# main.net
KiCad netlist of a schematic drawn in EAGLE
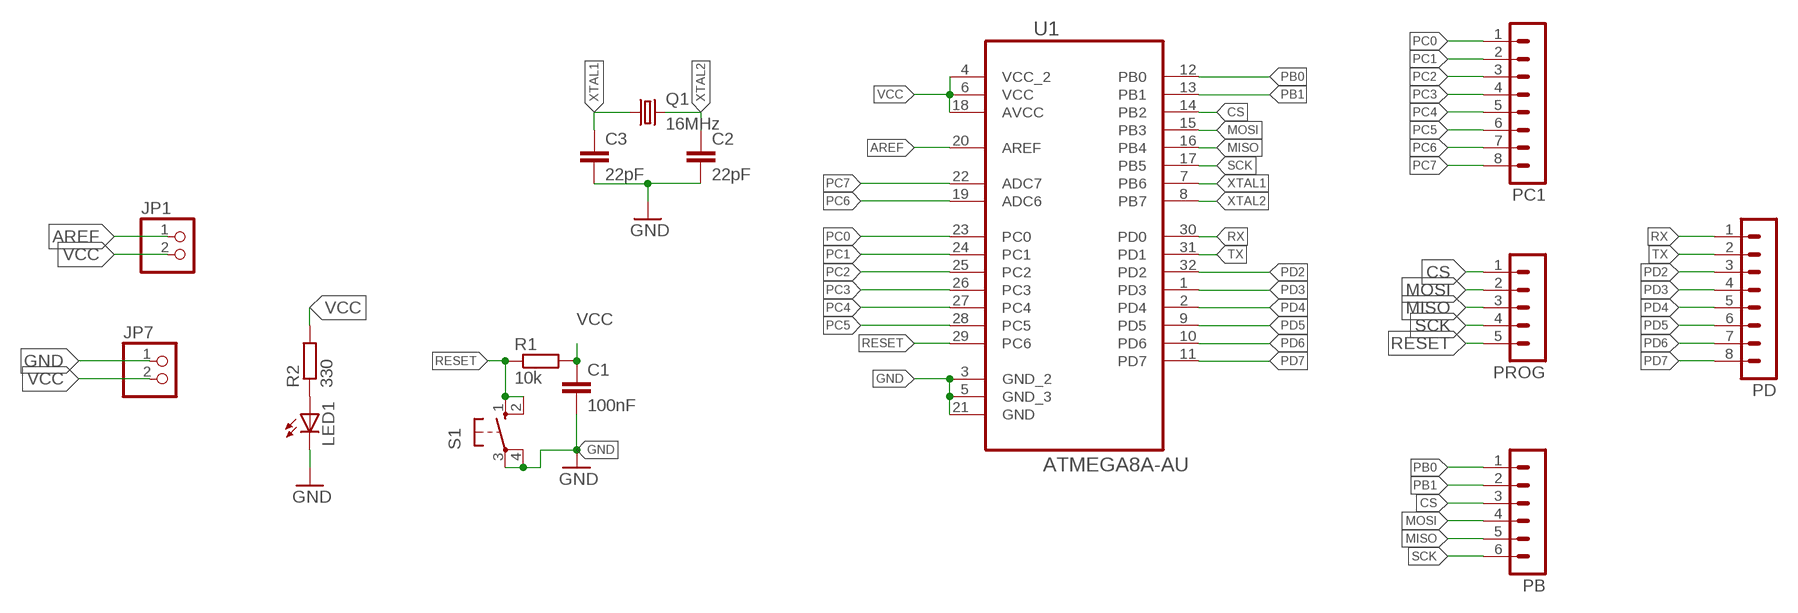
[diagram p0: schematic, sheet 1]

(export (version "E")
  (design (tool "Eeschema 10.0.6"))
  (components
    (comp (ref "C1")
      (value "100nF")
      (footprint "eagle-import:C025-025X050")
      (libsource (lib "eagle-import") (part "C-EU025-025X050"))
    )
    (comp (ref "C2")
      (value "22pF")
      (footprint "eagle-import:C025-025X050")
      (libsource (lib "eagle-import") (part "C-EU025-025X050"))
    )
    (comp (ref "C3")
      (value "22pF")
      (footprint "eagle-import:C025-025X050")
      (libsource (lib "eagle-import") (part "C-EU025-025X050"))
    )
    (comp (ref "JP1")
      (value "PINHD-1X2")
      (footprint "eagle-import:1X02")
      (libsource (lib "eagle-import") (part "PINHD-1X2"))
    )
    (comp (ref "JP7")
      (value "PINHD-1X2")
      (footprint "eagle-import:1X02")
      (libsource (lib "eagle-import") (part "PINHD-1X2"))
    )
    (comp (ref "LED1")
      (value "LED3MM")
      (footprint "eagle-import:LED3MM")
      (libsource (lib "eagle-import") (part "LED3MM"))
    )
    (comp (ref "PB")
      (value "MA06-1")
      (footprint "eagle-import:MA06-1")
      (libsource (lib "eagle-import") (part "MA06-1"))
    )
    (comp (ref "PC1")
      (value "MA08-1")
      (footprint "eagle-import:MA08-1")
      (libsource (lib "eagle-import") (part "MA08-1"))
    )
    (comp (ref "PD")
      (value "MA08-1")
      (footprint "eagle-import:MA08-1")
      (libsource (lib "eagle-import") (part "MA08-1"))
    )
    (comp (ref "PROG")
      (value "MA05-1")
      (footprint "eagle-import:MA05-1")
      (libsource (lib "eagle-import") (part "MA05-1"))
    )
    (comp (ref "Q1")
      (value "16MHz")
      (footprint "eagle-import:HC49_S")
      (libsource (lib "eagle-import") (part "CRYSTALHC49S"))
    )
    (comp (ref "R1")
      (value "10k")
      (footprint "eagle-import:M0805")
      (libsource (lib "eagle-import") (part "resistor_R-EU_M0805"))
    )
    (comp (ref "R2")
      (value "330")
      (footprint "eagle-import:M0805")
      (libsource (lib "eagle-import") (part "R-EU_M0805"))
    )
    (comp (ref "S1")
      (value "10-XX")
      (footprint "eagle-import:B3F-10XX")
      (fields (field (name "MPN") "B3F-1000"))
      (libsource (lib "eagle-import") (part "10-XX"))
    )
    (comp (ref "U1")
      (value "ATMEGA8A-AU")
      (footprint "eagle-import:QFP80P900X900X120-32N")
      (libsource (lib "eagle-import") (part "ATMEGA8A-AU"))
    )
  )
  (nets
    (net (code "1") (name "AREF") (class "Default")
      (node (ref "JP1") (pin "1") (pinfunction "1_1") (pintype "passive"))
      (node (ref "U1") (pin "20") (pinfunction "AREF_20") (pintype "input"))
    )
    (net (code "2") (name "CS") (class "Default")
      (node (ref "PB") (pin "3") (pinfunction "3_3") (pintype "passive"))
      (node (ref "PROG") (pin "1") (pinfunction "1_1") (pintype "passive"))
      (node (ref "U1") (pin "14") (pinfunction "PB2_14") (pintype "passive"))
    )
    (net (code "3") (name "GND") (class "Default")
      (node (ref "C1") (pin "2") (pinfunction "2_2") (pintype "passive"))
      (node (ref "C2") (pin "2") (pinfunction "2_2") (pintype "passive"))
      (node (ref "C3") (pin "2") (pinfunction "2_2") (pintype "passive"))
      (node (ref "JP7") (pin "1") (pinfunction "1_1") (pintype "passive"))
      (node (ref "LED1") (pin "K") (pinfunction "C_K") (pintype "passive"))
      (node (ref "S1") (pin "3") (pinfunction "P_3") (pintype "passive"))
      (node (ref "S1") (pin "4") (pinfunction "P1_4") (pintype "passive"))
      (node (ref "U1") (pin "21") (pinfunction "GND_21") (pintype "passive"))
      (node (ref "U1") (pin "3") (pinfunction "GND_2_3") (pintype "passive"))
      (node (ref "U1") (pin "5") (pinfunction "GND_3_5") (pintype "passive"))
    )
    (net (code "4") (name "MISO") (class "Default")
      (node (ref "PB") (pin "5") (pinfunction "5_5") (pintype "passive"))
      (node (ref "PROG") (pin "3") (pinfunction "3_3") (pintype "passive"))
      (node (ref "U1") (pin "16") (pinfunction "PB4_16") (pintype "passive"))
    )
    (net (code "5") (name "MOSI") (class "Default")
      (node (ref "PB") (pin "4") (pinfunction "4_4") (pintype "passive"))
      (node (ref "PROG") (pin "2") (pinfunction "2_2") (pintype "passive"))
      (node (ref "U1") (pin "15") (pinfunction "PB3_15") (pintype "passive"))
    )
    (net (code "6") (name "Net-(LED1-PadA)") (class "Default")
      (node (ref "LED1") (pin "A") (pinfunction "A_A") (pintype "passive"))
      (node (ref "R2") (pin "1") (pinfunction "1_1") (pintype "passive"))
    )
    (net (code "7") (name "PB0") (class "Default")
      (node (ref "PB") (pin "1") (pinfunction "1_1") (pintype "passive"))
      (node (ref "U1") (pin "12") (pinfunction "PB0_12") (pintype "passive"))
    )
    (net (code "8") (name "PB1") (class "Default")
      (node (ref "PB") (pin "2") (pinfunction "2_2") (pintype "passive"))
      (node (ref "U1") (pin "13") (pinfunction "PB1_13") (pintype "passive"))
    )
    (net (code "9") (name "PC0") (class "Default")
      (node (ref "PC1") (pin "1") (pinfunction "1_1") (pintype "passive"))
      (node (ref "U1") (pin "23") (pinfunction "PC0_23") (pintype "bidirectional"))
    )
    (net (code "10") (name "PC1") (class "Default")
      (node (ref "PC1") (pin "2") (pinfunction "2_2") (pintype "passive"))
      (node (ref "U1") (pin "24") (pinfunction "PC1_24") (pintype "bidirectional"))
    )
    (net (code "11") (name "PC2") (class "Default")
      (node (ref "PC1") (pin "3") (pinfunction "3_3") (pintype "passive"))
      (node (ref "U1") (pin "25") (pinfunction "PC2_25") (pintype "bidirectional"))
    )
    (net (code "12") (name "PC3") (class "Default")
      (node (ref "PC1") (pin "4") (pinfunction "4_4") (pintype "passive"))
      (node (ref "U1") (pin "26") (pinfunction "PC3_26") (pintype "bidirectional"))
    )
    (net (code "13") (name "PC4") (class "Default")
      (node (ref "PC1") (pin "5") (pinfunction "5_5") (pintype "passive"))
      (node (ref "U1") (pin "27") (pinfunction "PC4_27") (pintype "bidirectional"))
    )
    (net (code "14") (name "PC5") (class "Default")
      (node (ref "PC1") (pin "6") (pinfunction "6_6") (pintype "passive"))
      (node (ref "U1") (pin "28") (pinfunction "PC5_28") (pintype "bidirectional"))
    )
    (net (code "15") (name "PC6") (class "Default")
      (node (ref "PC1") (pin "7") (pinfunction "7_7") (pintype "passive"))
      (node (ref "U1") (pin "19") (pinfunction "ADC6_19") (pintype "input"))
    )
    (net (code "16") (name "PC7") (class "Default")
      (node (ref "PC1") (pin "8") (pinfunction "8_8") (pintype "passive"))
      (node (ref "U1") (pin "22") (pinfunction "ADC7_22") (pintype "input"))
    )
    (net (code "17") (name "PD2") (class "Default")
      (node (ref "PD") (pin "3") (pinfunction "3_3") (pintype "passive"))
      (node (ref "U1") (pin "32") (pinfunction "PD2_32") (pintype "bidirectional"))
    )
    (net (code "18") (name "PD3") (class "Default")
      (node (ref "PD") (pin "4") (pinfunction "4_4") (pintype "passive"))
      (node (ref "U1") (pin "1") (pinfunction "PD3_1") (pintype "bidirectional"))
    )
    (net (code "19") (name "PD4") (class "Default")
      (node (ref "PD") (pin "5") (pinfunction "5_5") (pintype "passive"))
      (node (ref "U1") (pin "2") (pinfunction "PD4_2") (pintype "bidirectional"))
    )
    (net (code "20") (name "PD5") (class "Default")
      (node (ref "PD") (pin "6") (pinfunction "6_6") (pintype "passive"))
      (node (ref "U1") (pin "9") (pinfunction "PD5_9") (pintype "passive"))
    )
    (net (code "21") (name "PD6") (class "Default")
      (node (ref "PD") (pin "7") (pinfunction "7_7") (pintype "passive"))
      (node (ref "U1") (pin "10") (pinfunction "PD6_10") (pintype "passive"))
    )
    (net (code "22") (name "PD7") (class "Default")
      (node (ref "PD") (pin "8") (pinfunction "8_8") (pintype "passive"))
      (node (ref "U1") (pin "11") (pinfunction "PD7_11") (pintype "passive"))
    )
    (net (code "23") (name "RESET") (class "Default")
      (node (ref "PROG") (pin "5") (pinfunction "5_5") (pintype "passive"))
      (node (ref "R1") (pin "1") (pinfunction "1_1") (pintype "passive"))
      (node (ref "S1") (pin "1") (pinfunction "S_1") (pintype "passive"))
      (node (ref "S1") (pin "2") (pinfunction "S1_2") (pintype "passive"))
      (node (ref "U1") (pin "29") (pinfunction "PC6_29") (pintype "bidirectional"))
    )
    (net (code "24") (name "RX") (class "Default")
      (node (ref "PD") (pin "1") (pinfunction "1_1") (pintype "passive"))
      (node (ref "U1") (pin "30") (pinfunction "PD0_30") (pintype "bidirectional"))
    )
    (net (code "25") (name "SCK") (class "Default")
      (node (ref "PB") (pin "6") (pinfunction "6_6") (pintype "passive"))
      (node (ref "PROG") (pin "4") (pinfunction "4_4") (pintype "passive"))
      (node (ref "U1") (pin "17") (pinfunction "PB5_17") (pintype "passive"))
    )
    (net (code "26") (name "TX") (class "Default")
      (node (ref "PD") (pin "2") (pinfunction "2_2") (pintype "passive"))
      (node (ref "U1") (pin "31") (pinfunction "PD1_31") (pintype "bidirectional"))
    )
    (net (code "27") (name "VCC") (class "Default")
      (node (ref "C1") (pin "1") (pinfunction "1_1") (pintype "passive"))
      (node (ref "JP1") (pin "2") (pinfunction "2_2") (pintype "passive"))
      (node (ref "JP7") (pin "2") (pinfunction "2_2") (pintype "passive"))
      (node (ref "R1") (pin "2") (pinfunction "2_2") (pintype "passive"))
      (node (ref "R2") (pin "2") (pinfunction "2_2") (pintype "passive"))
      (node (ref "U1") (pin "18") (pinfunction "AVCC_18") (pintype "power_in"))
      (node (ref "U1") (pin "4") (pinfunction "VCC_2_4") (pintype "power_in"))
      (node (ref "U1") (pin "6") (pinfunction "VCC_6") (pintype "power_in"))
    )
    (net (code "28") (name "XTAL1") (class "Default")
      (node (ref "C3") (pin "1") (pinfunction "1_1") (pintype "passive"))
      (node (ref "Q1") (pin "1") (pinfunction "1_1") (pintype "passive"))
      (node (ref "U1") (pin "7") (pinfunction "PB6_7") (pintype "bidirectional"))
    )
    (net (code "29") (name "XTAL2") (class "Default")
      (node (ref "C2") (pin "1") (pinfunction "1_1") (pintype "passive"))
      (node (ref "Q1") (pin "2") (pinfunction "2_2") (pintype "passive"))
      (node (ref "U1") (pin "8") (pinfunction "PB7_8") (pintype "passive"))
    )
  )
)
